# PANEL.net
KiCad netlist of a schematic drawn in Altium Designer
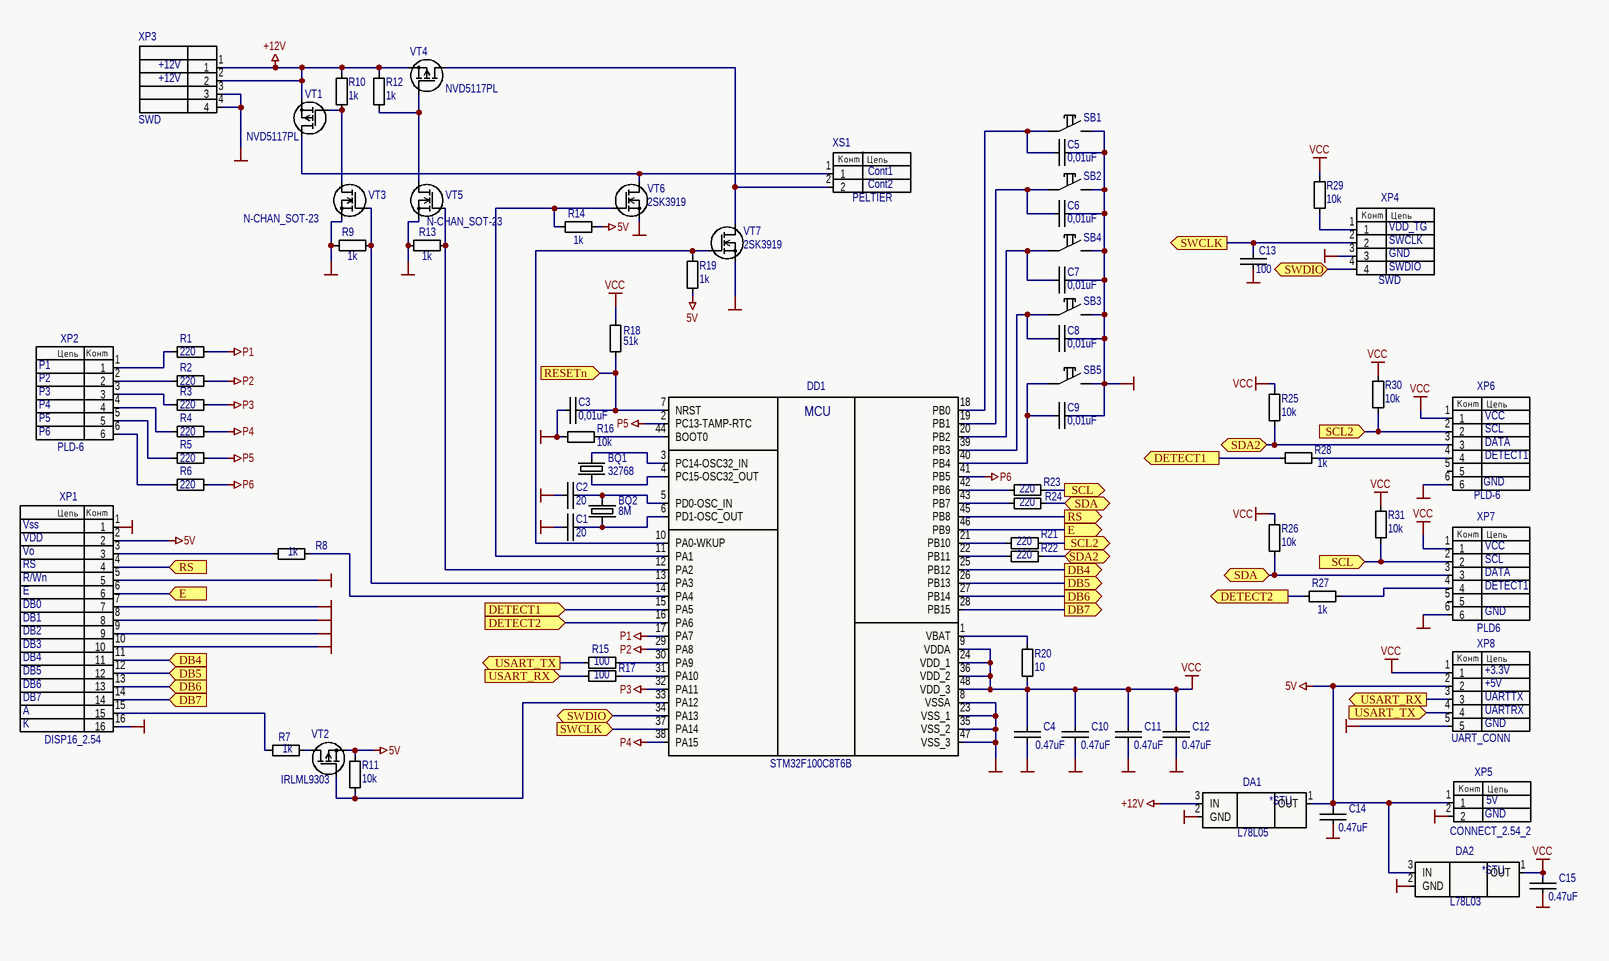
[diagram p0: PANEL.SchDoc]

(export (version "E")
  (design (tool "Eeschema 10.0.6"))
  (components
    (comp (ref "BQ1") (value "32768") (footprint "WatchQ") (libsource (lib "PANEL") (part "WatchQ")))
    (comp (ref "BQ2") (value "8M") (footprint "HC 49S") (libsource (lib "PANEL") (part "BQ_HC 49S")))
    (comp (ref "C1")
      (value "20")
      (footprint "Cap_0805")
      (fields (field (name "MANUFACTURER") "AVX") (field (name "PART NUMBER") "08051A200JAT2A"))
      (libsource (lib "PANEL") (part "Cap_0805"))
    )
    (comp (ref "C2")
      (value "20")
      (footprint "Cap_0805")
      (fields (field (name "MANUFACTURER") "AVX") (field (name "PART NUMBER") "08051A200JAT2A"))
      (libsource (lib "PANEL") (part "Cap_0805"))
    )
    (comp (ref "C3")
      (value "0,01uF")
      (footprint "Cap_0805")
      (fields (field (name "MANUFACTURER") "AVX") (field (name "PART NUMBER") "08055C103JAT2A"))
      (libsource (lib "PANEL") (part "Cap_0805"))
    )
    (comp (ref "C4")
      (value "0.47uF")
      (footprint "Cap_0805")
      (fields (field (name "MANUFACTURER") "AVX") (field (name "PART NUMBER") "0805YC475KAT2A"))
      (libsource (lib "PANEL") (part "Cap_0805"))
    )
    (comp (ref "C5")
      (value "0,01uF")
      (footprint "Cap_0805")
      (fields (field (name "MANUFACTURER") "AVX") (field (name "PART NUMBER") "08055C103JAT2A"))
      (libsource (lib "PANEL") (part "Cap_0805"))
    )
    (comp (ref "C6")
      (value "0,01uF")
      (footprint "Cap_0805")
      (fields (field (name "MANUFACTURER") "AVX") (field (name "PART NUMBER") "08055C103JAT2A"))
      (libsource (lib "PANEL") (part "Cap_0805"))
    )
    (comp (ref "C7")
      (value "0,01uF")
      (footprint "Cap_0805")
      (fields (field (name "MANUFACTURER") "AVX") (field (name "PART NUMBER") "08055C103JAT2A"))
      (libsource (lib "PANEL") (part "Cap_0805"))
    )
    (comp (ref "C8")
      (value "0,01uF")
      (footprint "Cap_0805")
      (fields (field (name "MANUFACTURER") "AVX") (field (name "PART NUMBER") "08055C103JAT2A"))
      (libsource (lib "PANEL") (part "Cap_0805"))
    )
    (comp (ref "C9")
      (value "0,01uF")
      (footprint "Cap_0805")
      (fields (field (name "MANUFACTURER") "AVX") (field (name "PART NUMBER") "08055C103JAT2A"))
      (libsource (lib "PANEL") (part "Cap_0805"))
    )
    (comp (ref "C10")
      (value "0.47uF")
      (footprint "Cap_0805")
      (fields (field (name "MANUFACTURER") "AVX") (field (name "PART NUMBER") "0805YC475KAT2A"))
      (libsource (lib "PANEL") (part "Cap_0805"))
    )
    (comp (ref "C11")
      (value "0.47uF")
      (footprint "Cap_0805")
      (fields (field (name "MANUFACTURER") "AVX") (field (name "PART NUMBER") "0805YC475KAT2A"))
      (libsource (lib "PANEL") (part "Cap_0805"))
    )
    (comp (ref "C12")
      (value "0.47uF")
      (footprint "Cap_0805")
      (fields (field (name "MANUFACTURER") "AVX") (field (name "PART NUMBER") "0805YC475KAT2A"))
      (libsource (lib "PANEL") (part "Cap_0805"))
    )
    (comp (ref "C13")
      (value "100")
      (footprint "Cap_0805")
      (fields (field (name "MANUFACTURER") "AVX") (field (name "PART NUMBER") "08055C101KAT2A"))
      (libsource (lib "PANEL") (part "Cap_0805"))
    )
    (comp (ref "C14")
      (value "0.47uF")
      (footprint "Cap_0805")
      (fields (field (name "MANUFACTURER") "AVX") (field (name "PART NUMBER") "0805YC475KAT2A"))
      (libsource (lib "PANEL") (part "Cap_0805"))
    )
    (comp (ref "C15")
      (value "0.47uF")
      (footprint "Cap_0805")
      (fields (field (name "MANUFACTURER") "AVX") (field (name "PART NUMBER") "0805YC475KAT2A"))
      (libsource (lib "PANEL") (part "Cap_0805"))
    )
    (comp (ref "DA1") (value "L78L05") (footprint "kren") (libsource (lib "PANEL") (part "kren")))
    (comp (ref "DA2")
      (value "L78L03")
      (footprint "kren")
      (fields (field (name "PART NUMBER") "L78L05"))
      (libsource (lib "PANEL") (part "kren"))
    )
    (comp (ref "DD1")
      (value "STM32F100C8T6B")
      (footprint "LQFP48")
      (fields (field (name "MANUFACTURER") "Manufacturer") (field (name "PART NUMBER") "Part Number"))
      (libsource (lib "PANEL") (part "STM32F100C8T6B"))
    )
    (comp (ref "R1") (value "220") (footprint "Res_0805") (libsource (lib "PANEL") (part "Res_0805")))
    (comp (ref "R2") (value "220") (footprint "Res_0805") (libsource (lib "PANEL") (part "Res_0805")))
    (comp (ref "R3") (value "220") (footprint "Res_0805") (libsource (lib "PANEL") (part "Res_0805")))
    (comp (ref "R4")
      (value "220")
      (footprint "Res_0805")
      (fields (field (name "MANUFACTURER") "Vishay") (field (name "PART NUMBER") "CRCW080510K0JNTA"))
      (libsource (lib "PANEL") (part "Res_0805"))
    )
    (comp (ref "R5")
      (value "220")
      (footprint "Res_0805")
      (fields (field (name "MANUFACTURER") "Vishay") (field (name "PART NUMBER") "CRCW080510K0JNTA"))
      (libsource (lib "PANEL") (part "Res_0805"))
    )
    (comp (ref "R6") (value "220") (footprint "Res_0805") (libsource (lib "PANEL") (part "Res_0805")))
    (comp (ref "R7") (value "1k") (footprint "Res_0805") (libsource (lib "PANEL") (part "Res_0805")))
    (comp (ref "R8") (value "1k") (footprint "Res_0805") (libsource (lib "PANEL") (part "Res_0805")))
    (comp (ref "R9") (value "1k") (footprint "Res_0805") (libsource (lib "PANEL") (part "Res_0805")))
    (comp (ref "R10")
      (value "1k")
      (footprint "Res_0805")
      (fields (field (name "MANUFACTURER") "Vishay") (field (name "PART NUMBER") "SMD 0805"))
      (libsource (lib "") (part "Res_0805_1"))
    )
    (comp (ref "R11")
      (value "10k")
      (footprint "Res_0805")
      (fields (field (name "MANUFACTURER") "Vishay") (field (name "PART NUMBER") "CRCW080510K0JNTA"))
      (libsource (lib "PANEL") (part "Res_0805"))
    )
    (comp (ref "R12") (value "1k") (footprint "Res_0805") (libsource (lib "") (part "Res_0805_1")))
    (comp (ref "R13") (value "1k") (footprint "Res_0805") (libsource (lib "PANEL") (part "Res_0805")))
    (comp (ref "R14")
      (value "1k")
      (footprint "Res_0805")
      (fields (field (name "PART NUMBER") "0805 1k"))
      (libsource (lib "PANEL") (part "Res_0805"))
    )
    (comp (ref "R15") (value "100") (footprint "Res_0805") (libsource (lib "PANEL") (part "Res_0805")))
    (comp (ref "R16")
      (value "10k")
      (footprint "Res_0805")
      (fields (field (name "MANUFACTURER") "Vishay") (field (name "PART NUMBER") "CRCW080510K0JNTA"))
      (libsource (lib "PANEL") (part "Res_0805"))
    )
    (comp (ref "R17") (value "100") (footprint "Res_0805") (libsource (lib "PANEL") (part "Res_0805")))
    (comp (ref "R18")
      (value "51k")
      (footprint "Res_0805")
      (fields (field (name "MANUFACTURER") "Vishay") (field (name "PART NUMBER") "CRCW08055K00JNTA"))
      (libsource (lib "PANEL") (part "Res_0805"))
    )
    (comp (ref "R19")
      (value "1k")
      (footprint "Res_0805")
      (fields (field (name "PART NUMBER") "0805 1k"))
      (libsource (lib "PANEL") (part "Res_0805"))
    )
    (comp (ref "R20")
      (value "10")
      (footprint "Res_0805")
      (fields (field (name "MANUFACTURER") "Vishay") (field (name "PART NUMBER") "CRCW080510R0FKEA"))
      (libsource (lib "PANEL") (part "Res_0805"))
    )
    (comp (ref "R21") (value "220") (footprint "Res_0805") (libsource (lib "PANEL") (part "Res_0805")))
    (comp (ref "R22") (value "220") (footprint "Res_0805") (libsource (lib "PANEL") (part "Res_0805")))
    (comp (ref "R23") (value "220") (footprint "Res_0805") (libsource (lib "PANEL") (part "Res_0805")))
    (comp (ref "R24") (value "220") (footprint "Res_0805") (libsource (lib "PANEL") (part "Res_0805")))
    (comp (ref "R25")
      (value "10k")
      (footprint "Res_0805")
      (fields (field (name "MANUFACTURER") "Vishay") (field (name "PART NUMBER") "CRCW080510K0JNTA"))
      (libsource (lib "PANEL") (part "Res_0805"))
    )
    (comp (ref "R26")
      (value "10k")
      (footprint "Res_0805")
      (fields (field (name "MANUFACTURER") "Vishay") (field (name "PART NUMBER") "CRCW080510K0JNTA"))
      (libsource (lib "PANEL") (part "Res_0805"))
    )
    (comp (ref "R27")
      (value "1k")
      (footprint "Res_0805")
      (fields (field (name "MANUFACTURER") "Vishay") (field (name "PART NUMBER") "CRCW080510K0JNTA"))
      (libsource (lib "PANEL") (part "Res_0805"))
    )
    (comp (ref "R28")
      (value "1k")
      (footprint "Res_0805")
      (fields (field (name "MANUFACTURER") "Vishay") (field (name "PART NUMBER") "CRCW080510K0JNTA"))
      (libsource (lib "PANEL") (part "Res_0805"))
    )
    (comp (ref "R29")
      (value "10k")
      (footprint "Res_0805")
      (fields (field (name "MANUFACTURER") "Vishay") (field (name "PART NUMBER") "CRCW080510K0JNTA"))
      (libsource (lib "PANEL") (part "Res_0805"))
    )
    (comp (ref "R30")
      (value "10k")
      (footprint "Res_0805")
      (fields (field (name "MANUFACTURER") "Vishay") (field (name "PART NUMBER") "CRCW080510K0JNTA"))
      (libsource (lib "PANEL") (part "Res_0805"))
    )
    (comp (ref "R31")
      (value "10k")
      (footprint "Res_0805")
      (fields (field (name "MANUFACTURER") "Vishay") (field (name "PART NUMBER") "CRCW080510K0JNTA"))
      (libsource (lib "PANEL") (part "Res_0805"))
    )
    (comp (ref "SB1")
      (value "TS A3PV 130")
      (footprint "TS A3PV 130")
      (description "Button")
      (libsource (lib "") (part "TS A3PV 130_1"))
    )
    (comp (ref "SB2")
      (value "TS A3PV 130")
      (footprint "TS A3PV 130")
      (description "Button")
      (libsource (lib "") (part "TS A3PV 130_2"))
    )
    (comp (ref "SB3")
      (value "TS A3PV 130")
      (footprint "TS A3PV 130")
      (description "Button")
      (libsource (lib "PANEL") (part "TS A3PV 130"))
    )
    (comp (ref "SB4")
      (value "TS A3PV 130")
      (footprint "TS A3PV 130")
      (description "Button")
      (libsource (lib "PANEL") (part "TS A3PV 130"))
    )
    (comp (ref "SB5")
      (value "TS A3PV 130")
      (footprint "TS A3PV 130")
      (description "Button")
      (libsource (lib "PANEL") (part "TS A3PV 130"))
    )
    (comp (ref "VT1") (value "NVD5117PL") (footprint "TO-252") (libsource (lib "") (part "P-CHAN_TO-252_1")))
    (comp (ref "VT2")
      (value "IRLML9303")
      (footprint "SOT-23")
      (fields (field (name "PART NUMBER") "IRLML9303TRPBF"))
      (libsource (lib "PSU") (part "P-CHAN_SOT-23"))
    )
    (comp (ref "VT3")
      (value "N-CHAN_SOT-23")
      (footprint "SOT-23")
      (libsource (lib "PANEL") (part "N-CHAN_SOT-23"))
    )
    (comp (ref "VT4")
      (value "NVD5117PL")
      (footprint "TO-252")
      (libsource (lib "PANEL") (part "P-CHAN_TO-252"))
    )
    (comp (ref "VT5")
      (value "N-CHAN_SOT-23")
      (footprint "SOT-23")
      (libsource (lib "PANEL") (part "N-CHAN_SOT-23"))
    )
    (comp (ref "VT6") (value "2SK3919") (footprint "TO-252") (libsource (lib "PANEL") (part "N-CHAN_TO-252")))
    (comp (ref "VT7") (value "2SK3919") (footprint "TO-252") (libsource (lib "PANEL") (part "N-CHAN_TO-252")))
    (comp (ref "XP1")
      (value "DISP16_2.54")
      (footprint "DISP16_2.54")
      (libsource (lib "PANEL") (part "DISP16_2.54"))
    )
    (comp (ref "XP2")
      (value "PLD-6")
      (footprint "CONN_2.54_6_2")
      (libsource (lib "PANEL") (part "CONNECT_2.54_6_2"))
    )
    (comp (ref "XP3")
      (value "SWD")
      (footprint "CONN_2.54_4")
      (fields (field (name "MANUFACTURER") "Manufacturer") (field (name "PART NUMBER") "Part Number"))
      (libsource (lib "PANEL") (part "CONNECT_SWD"))
    )
    (comp (ref "XP4")
      (value "SWD")
      (footprint "CONN_2.54_4")
      (fields (field (name "MANUFACTURER") "Manufacturer") (field (name "PART NUMBER") "Part Number"))
      (libsource (lib "") (part "CONNECT_SWD_1"))
    )
    (comp (ref "XP5")
      (value "CONNECT_2.54_2")
      (footprint "CONN_2.54_2")
      (libsource (lib "PANEL") (part "CONNECT_2.54_2"))
    )
    (comp (ref "XP6")
      (value "PLD-6")
      (footprint "CONN_2.54_6_2")
      (libsource (lib "PANEL") (part "CONNECT_2.54_6_2"))
    )
    (comp (ref "XP7")
      (value "PLD6")
      (footprint "CONN_2.54_6_2")
      (libsource (lib "PANEL") (part "CONNECT_2.54_6_2"))
    )
    (comp (ref "XP8")
      (value "UART_CONN")
      (footprint "CONN_2.54_5")
      (libsource (lib "PANEL") (part "CONNECT_2.54_5"))
    )
    (comp (ref "XS1") (value "PELTIER") (footprint "PELTIER") (libsource (lib "PANEL") (part "PELTIER")))
  )
  (nets
    (net (code "1") (name "+12V") (class "Default")
      (node (ref "DA1") (pin "3") (pinfunction "IN_3") (pintype "passive"))
      (node (ref "R10") (pin "1") (pinfunction "1_1") (pintype "passive"))
      (node (ref "R12") (pin "2") (pinfunction "2_2") (pintype "passive"))
      (node (ref "VT1") (pin "3") (pinfunction "3_3") (pintype "passive"))
      (node (ref "VT4") (pin "3") (pinfunction "3_3") (pintype "passive"))
      (node (ref "XP3") (pin "1") (pinfunction "1_1") (pintype "passive"))
      (node (ref "XP3") (pin "2") (pinfunction "2_2") (pintype "passive"))
    )
    (net (code "2") (name "/DB4") (class "Default")
      (node (ref "DD1") (pin "25") (pinfunction "PB12_25") (pintype "passive"))
      (node (ref "XP1") (pin "11") (pinfunction "11_11") (pintype "passive"))
    )
    (net (code "3") (name "/DB5") (class "Default")
      (node (ref "DD1") (pin "26") (pinfunction "PB13_26") (pintype "passive"))
      (node (ref "XP1") (pin "12") (pinfunction "12_12") (pintype "passive"))
    )
    (net (code "4") (name "/DB6") (class "Default")
      (node (ref "DD1") (pin "27") (pinfunction "PB14_27") (pintype "passive"))
      (node (ref "XP1") (pin "13") (pinfunction "13_13") (pintype "passive"))
    )
    (net (code "5") (name "/DB7") (class "Default")
      (node (ref "DD1") (pin "28") (pinfunction "PB15_28") (pintype "passive"))
      (node (ref "XP1") (pin "14") (pinfunction "14_14") (pintype "passive"))
    )
    (net (code "6") (name "/DETECT1") (class "Default")
      (node (ref "DD1") (pin "15") (pinfunction "PA5_15") (pintype "passive"))
      (node (ref "R28") (pin "2") (pinfunction "2_2") (pintype "passive"))
    )
    (net (code "7") (name "/DETECT2") (class "Default")
      (node (ref "DD1") (pin "16") (pinfunction "PA6_16") (pintype "passive"))
      (node (ref "R27") (pin "2") (pinfunction "2_2") (pintype "passive"))
    )
    (net (code "8") (name "/E") (class "Default")
      (node (ref "DD1") (pin "46") (pinfunction "PB9_46") (pintype "passive"))
      (node (ref "XP1") (pin "6") (pinfunction "6_6") (pintype "passive"))
    )
    (net (code "9") (name "/RESETn") (class "Default")
      (node (ref "C3") (pin "2") (pinfunction "2_2") (pintype "passive"))
      (node (ref "DD1") (pin "7") (pinfunction "NRST_7") (pintype "passive"))
      (node (ref "R18") (pin "1") (pinfunction "1_1") (pintype "passive"))
    )
    (net (code "10") (name "/RS") (class "Default")
      (node (ref "DD1") (pin "45") (pinfunction "PB8_45") (pintype "passive"))
      (node (ref "XP1") (pin "4") (pinfunction "4_4") (pintype "passive"))
    )
    (net (code "11") (name "/SCL") (class "Default")
      (node (ref "R23") (pin "1") (pinfunction "1_1") (pintype "passive"))
      (node (ref "R31") (pin "1") (pinfunction "1_1") (pintype "passive"))
      (node (ref "XP7") (pin "2") (pinfunction "2_2") (pintype "passive"))
    )
    (net (code "12") (name "/SCL2") (class "Default")
      (node (ref "R21") (pin "1") (pinfunction "1_1") (pintype "passive"))
      (node (ref "R30") (pin "1") (pinfunction "1_1") (pintype "passive"))
      (node (ref "XP6") (pin "2") (pinfunction "2_2") (pintype "passive"))
    )
    (net (code "13") (name "/SDA") (class "Default")
      (node (ref "R24") (pin "1") (pinfunction "1_1") (pintype "passive"))
      (node (ref "R26") (pin "1") (pinfunction "1_1") (pintype "passive"))
      (node (ref "XP7") (pin "3") (pinfunction "3_3") (pintype "passive"))
    )
    (net (code "14") (name "/SDA2") (class "Default")
      (node (ref "R22") (pin "1") (pinfunction "1_1") (pintype "passive"))
      (node (ref "R25") (pin "1") (pinfunction "1_1") (pintype "passive"))
      (node (ref "XP6") (pin "3") (pinfunction "3_3") (pintype "passive"))
    )
    (net (code "15") (name "/SWCLK") (class "Default")
      (node (ref "C13") (pin "2") (pinfunction "2_2") (pintype "passive"))
      (node (ref "DD1") (pin "37") (pinfunction "PA14_37") (pintype "passive"))
      (node (ref "XP4") (pin "2") (pinfunction "2_2") (pintype "passive"))
    )
    (net (code "16") (name "/SWDIO") (class "Default")
      (node (ref "DD1") (pin "34") (pinfunction "PA13_34") (pintype "passive"))
      (node (ref "XP4") (pin "4") (pinfunction "4_4") (pintype "passive"))
    )
    (net (code "17") (name "/USART_RX") (class "Default")
      (node (ref "R17") (pin "1") (pinfunction "1_1") (pintype "passive"))
      (node (ref "XP8") (pin "3") (pinfunction "3_3") (pintype "passive"))
    )
    (net (code "18") (name "/USART_TX") (class "Default")
      (node (ref "R15") (pin "1") (pinfunction "1_1") (pintype "passive"))
      (node (ref "XP8") (pin "4") (pinfunction "4_4") (pintype "passive"))
    )
    (net (code "19") (name "5V") (class "Default")
      (node (ref "C14") (pin "2") (pinfunction "2_2") (pintype "passive"))
      (node (ref "DA1") (pin "1") (pinfunction "OUT_1") (pintype "passive"))
      (node (ref "DA2") (pin "3") (pinfunction "IN_3") (pintype "passive"))
      (node (ref "R11") (pin "1") (pinfunction "1_1") (pintype "passive"))
      (node (ref "R14") (pin "2") (pinfunction "2_2") (pintype "passive"))
      (node (ref "R19") (pin "1") (pinfunction "1_1") (pintype "passive"))
      (node (ref "VT2") (pin "2") (pinfunction "2_2") (pintype "passive"))
      (node (ref "XP1") (pin "2") (pinfunction "2_2") (pintype "passive"))
      (node (ref "XP5") (pin "1") (pinfunction "1_1") (pintype "passive"))
      (node (ref "XP8") (pin "2") (pinfunction "2_2") (pintype "passive"))
    )
    (net (code "20") (name "GND") (class "Default")
      (node (ref "C1") (pin "1") (pinfunction "1_1") (pintype "passive"))
      (node (ref "C10") (pin "1") (pinfunction "1_1") (pintype "passive"))
      (node (ref "C11") (pin "1") (pinfunction "1_1") (pintype "passive"))
      (node (ref "C12") (pin "1") (pinfunction "1_1") (pintype "passive"))
      (node (ref "C13") (pin "1") (pinfunction "1_1") (pintype "passive"))
      (node (ref "C14") (pin "1") (pinfunction "1_1") (pintype "passive"))
      (node (ref "C15") (pin "1") (pinfunction "1_1") (pintype "passive"))
      (node (ref "C2") (pin "1") (pinfunction "1_1") (pintype "passive"))
      (node (ref "C3") (pin "1") (pinfunction "1_1") (pintype "passive"))
      (node (ref "C4") (pin "1") (pinfunction "1_1") (pintype "passive"))
      (node (ref "C5") (pin "2") (pinfunction "2_2") (pintype "passive"))
      (node (ref "C6") (pin "2") (pinfunction "2_2") (pintype "passive"))
      (node (ref "C7") (pin "2") (pinfunction "2_2") (pintype "passive"))
      (node (ref "C8") (pin "2") (pinfunction "2_2") (pintype "passive"))
      (node (ref "C9") (pin "2") (pinfunction "2_2") (pintype "passive"))
      (node (ref "DA1") (pin "2") (pinfunction "GND_2") (pintype "passive"))
      (node (ref "DA2") (pin "2") (pinfunction "GND_2") (pintype "passive"))
      (node (ref "DD1") (pin "23") (pinfunction "VSS_1_23") (pintype "passive"))
      (node (ref "DD1") (pin "35") (pinfunction "VSS_2_35") (pintype "passive"))
      (node (ref "DD1") (pin "47") (pinfunction "VSS_3_47") (pintype "passive"))
      (node (ref "DD1") (pin "8") (pinfunction "VSSA_8") (pintype "passive"))
      (node (ref "R13") (pin "1") (pinfunction "1_1") (pintype "passive"))
      (node (ref "R16") (pin "2") (pinfunction "2_2") (pintype "passive"))
      (node (ref "R9") (pin "2") (pinfunction "2_2") (pintype "passive"))
      (node (ref "SB1") (pin "2") (pinfunction "IN_2") (pintype "passive"))
      (node (ref "SB2") (pin "2") (pinfunction "IN_2") (pintype "passive"))
      (node (ref "SB3") (pin "2") (pinfunction "IN_2") (pintype "passive"))
      (node (ref "SB4") (pin "2") (pinfunction "IN_2") (pintype "passive"))
      (node (ref "SB5") (pin "2") (pinfunction "IN_2") (pintype "passive"))
      (node (ref "VT3") (pin "2") (pinfunction "2_2") (pintype "passive"))
      (node (ref "VT5") (pin "2") (pinfunction "2_2") (pintype "passive"))
      (node (ref "VT6") (pin "3") (pinfunction "3_3") (pintype "passive"))
      (node (ref "VT7") (pin "3") (pinfunction "3_3") (pintype "passive"))
      (node (ref "XP1") (pin "1") (pinfunction "1_1") (pintype "passive"))
      (node (ref "XP1") (pin "10") (pinfunction "10_10") (pintype "passive"))
      (node (ref "XP1") (pin "16") (pinfunction "16_16") (pintype "passive"))
      (node (ref "XP1") (pin "5") (pinfunction "5_5") (pintype "passive"))
      (node (ref "XP1") (pin "7") (pinfunction "7_7") (pintype "passive"))
      (node (ref "XP1") (pin "8") (pinfunction "8_8") (pintype "passive"))
      (node (ref "XP1") (pin "9") (pinfunction "9_9") (pintype "passive"))
      (node (ref "XP3") (pin "3") (pinfunction "3_3") (pintype "passive"))
      (node (ref "XP3") (pin "4") (pinfunction "4_4") (pintype "passive"))
      (node (ref "XP4") (pin "3") (pinfunction "3_3") (pintype "passive"))
      (node (ref "XP5") (pin "2") (pinfunction "2_2") (pintype "passive"))
      (node (ref "XP6") (pin "6") (pinfunction "6_6") (pintype "passive"))
      (node (ref "XP7") (pin "6") (pinfunction "6_6") (pintype "passive"))
      (node (ref "XP8") (pin "5") (pinfunction "5_5") (pintype "passive"))
    )
    (net (code "21") (name "Net-(DD1-BOOT0)") (class "Default")
      (node (ref "DD1") (pin "44") (pinfunction "BOOT0_44") (pintype "passive"))
      (node (ref "R16") (pin "1") (pinfunction "1_1") (pintype "passive"))
    )
    (net (code "22") (name "Net-(DD1-PA0-WKUP)") (class "Default")
      (node (ref "DD1") (pin "10") (pinfunction "PA0-WKUP_10") (pintype "passive"))
      (node (ref "R19") (pin "2") (pinfunction "2_2") (pintype "passive"))
      (node (ref "VT7") (pin "1") (pinfunction "1_1") (pintype "passive"))
    )
    (net (code "23") (name "Net-(DD1-PA1)") (class "Default")
      (node (ref "DD1") (pin "11") (pinfunction "PA1_11") (pintype "passive"))
      (node (ref "R14") (pin "1") (pinfunction "1_1") (pintype "passive"))
      (node (ref "VT6") (pin "1") (pinfunction "1_1") (pintype "passive"))
    )
    (net (code "24") (name "Net-(DD1-PA2)") (class "Default")
      (node (ref "DD1") (pin "12") (pinfunction "PA2_12") (pintype "passive"))
      (node (ref "R13") (pin "2") (pinfunction "2_2") (pintype "passive"))
      (node (ref "VT5") (pin "1") (pinfunction "1_1") (pintype "passive"))
    )
    (net (code "25") (name "Net-(DD1-PA3)") (class "Default")
      (node (ref "DD1") (pin "13") (pinfunction "PA3_13") (pintype "passive"))
      (node (ref "R9") (pin "1") (pinfunction "1_1") (pintype "passive"))
      (node (ref "VT3") (pin "1") (pinfunction "1_1") (pintype "passive"))
    )
    (net (code "26") (name "Net-(DD1-PA4)") (class "Default")
      (node (ref "DD1") (pin "14") (pinfunction "PA4_14") (pintype "passive"))
      (node (ref "R8") (pin "1") (pinfunction "1_1") (pintype "passive"))
    )
    (net (code "27") (name "Net-(DD1-PA9)") (class "Default")
      (node (ref "DD1") (pin "30") (pinfunction "PA9_30") (pintype "passive"))
      (node (ref "R15") (pin "2") (pinfunction "2_2") (pintype "passive"))
    )
    (net (code "28") (name "Net-(DD1-PA10)") (class "Default")
      (node (ref "DD1") (pin "31") (pinfunction "PA10_31") (pintype "passive"))
      (node (ref "R17") (pin "2") (pinfunction "2_2") (pintype "passive"))
    )
    (net (code "29") (name "Net-(DD1-PA12)") (class "Default")
      (node (ref "DD1") (pin "33") (pinfunction "PA12_33") (pintype "passive"))
      (node (ref "R11") (pin "2") (pinfunction "2_2") (pintype "passive"))
      (node (ref "VT2") (pin "1") (pinfunction "1_1") (pintype "passive"))
    )
    (net (code "30") (name "Net-(DD1-PB0)") (class "Default")
      (node (ref "C5") (pin "1") (pinfunction "1_1") (pintype "passive"))
      (node (ref "DD1") (pin "18") (pinfunction "PB0_18") (pintype "passive"))
      (node (ref "SB1") (pin "1") (pinfunction "OUT_1") (pintype "passive"))
    )
    (net (code "31") (name "Net-(DD1-PB1)") (class "Default")
      (node (ref "C6") (pin "1") (pinfunction "1_1") (pintype "passive"))
      (node (ref "DD1") (pin "19") (pinfunction "PB1_19") (pintype "passive"))
      (node (ref "SB2") (pin "1") (pinfunction "OUT_1") (pintype "passive"))
    )
    (net (code "32") (name "Net-(DD1-PB2)") (class "Default")
      (node (ref "C7") (pin "1") (pinfunction "1_1") (pintype "passive"))
      (node (ref "DD1") (pin "20") (pinfunction "PB2_20") (pintype "passive"))
      (node (ref "SB4") (pin "1") (pinfunction "OUT_1") (pintype "passive"))
    )
    (net (code "33") (name "Net-(DD1-PB3)") (class "Default")
      (node (ref "C8") (pin "1") (pinfunction "1_1") (pintype "passive"))
      (node (ref "DD1") (pin "39") (pinfunction "PB3_39") (pintype "passive"))
      (node (ref "SB3") (pin "1") (pinfunction "OUT_1") (pintype "passive"))
    )
    (net (code "34") (name "Net-(DD1-PB4)") (class "Default")
      (node (ref "C9") (pin "1") (pinfunction "1_1") (pintype "passive"))
      (node (ref "DD1") (pin "40") (pinfunction "PB4_40") (pintype "passive"))
      (node (ref "SB5") (pin "1") (pinfunction "OUT_1") (pintype "passive"))
    )
    (net (code "35") (name "Net-(DD1-PB6)") (class "Default")
      (node (ref "DD1") (pin "42") (pinfunction "PB6_42") (pintype "passive"))
      (node (ref "R23") (pin "2") (pinfunction "2_2") (pintype "passive"))
    )
    (net (code "36") (name "Net-(DD1-PB7)") (class "Default")
      (node (ref "DD1") (pin "43") (pinfunction "PB7_43") (pintype "passive"))
      (node (ref "R24") (pin "2") (pinfunction "2_2") (pintype "passive"))
    )
    (net (code "37") (name "Net-(DD1-PB10)") (class "Default")
      (node (ref "DD1") (pin "21") (pinfunction "PB10_21") (pintype "passive"))
      (node (ref "R21") (pin "2") (pinfunction "2_2") (pintype "passive"))
    )
    (net (code "38") (name "Net-(DD1-PB11)") (class "Default")
      (node (ref "DD1") (pin "22") (pinfunction "PB11_22") (pintype "passive"))
      (node (ref "R22") (pin "2") (pinfunction "2_2") (pintype "passive"))
    )
    (net (code "39") (name "Net-(DD1-PC14-OSC32_IN)") (class "Default")
      (node (ref "BQ1") (pin "1") (pinfunction "1_1") (pintype "passive"))
      (node (ref "DD1") (pin "3") (pinfunction "PC14-OSC32_IN_3") (pintype "passive"))
    )
    (net (code "40") (name "Net-(DD1-PC15-OSC32_OUT)") (class "Default")
      (node (ref "BQ1") (pin "2") (pinfunction "2_2") (pintype "passive"))
      (node (ref "DD1") (pin "4") (pinfunction "PC15-OSC32_OUT_4") (pintype "passive"))
    )
    (net (code "41") (name "Net-(DD1-PD0-OSC_IN)") (class "Default")
      (node (ref "BQ2") (pin "2") (pinfunction "2_2") (pintype "passive"))
      (node (ref "C2") (pin "2") (pinfunction "2_2") (pintype "passive"))
      (node (ref "DD1") (pin "5") (pinfunction "PD0-OSC_IN_5") (pintype "passive"))
    )
    (net (code "42") (name "Net-(DD1-PD1-OSC_OUT)") (class "Default")
      (node (ref "BQ2") (pin "1") (pinfunction "1_1") (pintype "passive"))
      (node (ref "C1") (pin "2") (pinfunction "2_2") (pintype "passive"))
      (node (ref "DD1") (pin "6") (pinfunction "PD1-OSC_OUT_6") (pintype "passive"))
    )
    (net (code "43") (name "Net-(DD1-VBAT)") (class "Default")
      (node (ref "DD1") (pin "1") (pinfunction "VBAT_1") (pintype "passive"))
      (node (ref "R20") (pin "1") (pinfunction "1_1") (pintype "passive"))
    )
    (net (code "44") (name "Net-(R1-Pad1)") (class "Default")
      (node (ref "R1") (pin "1") (pinfunction "1_1") (pintype "passive"))
      (node (ref "XP2") (pin "1") (pinfunction "1_1") (pintype "passive"))
    )
    (net (code "45") (name "Net-(R2-Pad1)") (class "Default")
      (node (ref "R2") (pin "1") (pinfunction "1_1") (pintype "passive"))
      (node (ref "XP2") (pin "2") (pinfunction "2_2") (pintype "passive"))
    )
    (net (code "46") (name "Net-(R3-Pad1)") (class "Default")
      (node (ref "R3") (pin "1") (pinfunction "1_1") (pintype "passive"))
      (node (ref "XP2") (pin "3") (pinfunction "3_3") (pintype "passive"))
    )
    (net (code "47") (name "Net-(R4-Pad2)") (class "Default")
      (node (ref "R4") (pin "2") (pinfunction "2_2") (pintype "passive"))
      (node (ref "XP2") (pin "4") (pinfunction "4_4") (pintype "passive"))
    )
    (net (code "48") (name "Net-(R5-Pad2)") (class "Default")
      (node (ref "R5") (pin "2") (pinfunction "2_2") (pintype "passive"))
      (node (ref "XP2") (pin "5") (pinfunction "5_5") (pintype "passive"))
    )
    (net (code "49") (name "Net-(R6-Pad1)") (class "Default")
      (node (ref "R6") (pin "1") (pinfunction "1_1") (pintype "passive"))
      (node (ref "XP2") (pin "6") (pinfunction "6_6") (pintype "passive"))
    )
    (net (code "50") (name "Net-(R7-Pad1)") (class "Default")
      (node (ref "R7") (pin "1") (pinfunction "1_1") (pintype "passive"))
      (node (ref "VT2") (pin "3") (pinfunction "3_3") (pintype "passive"))
    )
    (net (code "51") (name "Net-(R7-Pad2)") (class "Default")
      (node (ref "R7") (pin "2") (pinfunction "2_2") (pintype "passive"))
      (node (ref "XP1") (pin "15") (pinfunction "15_15") (pintype "passive"))
    )
    (net (code "52") (name "Net-(R8-Pad2)") (class "Default")
      (node (ref "R8") (pin "2") (pinfunction "2_2") (pintype "passive"))
      (node (ref "XP1") (pin "3") (pinfunction "3_3") (pintype "passive"))
    )
    (net (code "53") (name "Net-(R10-Pad2)") (class "Default")
      (node (ref "R10") (pin "2") (pinfunction "2_2") (pintype "passive"))
      (node (ref "VT1") (pin "1") (pinfunction "1_1") (pintype "passive"))
      (node (ref "VT3") (pin "3") (pinfunction "3_3") (pintype "passive"))
    )
    (net (code "54") (name "Net-(R12-Pad1)") (class "Default")
      (node (ref "R12") (pin "1") (pinfunction "1_1") (pintype "passive"))
      (node (ref "VT4") (pin "1") (pinfunction "1_1") (pintype "passive"))
      (node (ref "VT5") (pin "3") (pinfunction "3_3") (pintype "passive"))
    )
    (net (code "55") (name "Net-(R27-Pad1)") (class "Default")
      (node (ref "R27") (pin "1") (pinfunction "1_1") (pintype "passive"))
      (node (ref "XP7") (pin "4") (pinfunction "4_4") (pintype "passive"))
    )
    (net (code "56") (name "Net-(R28-Pad1)") (class "Default")
      (node (ref "R28") (pin "1") (pinfunction "1_1") (pintype "passive"))
      (node (ref "XP6") (pin "4") (pinfunction "4_4") (pintype "passive"))
    )
    (net (code "57") (name "Net-(R29-Pad1)") (class "Default")
      (node (ref "R29") (pin "1") (pinfunction "1_1") (pintype "passive"))
      (node (ref "XP4") (pin "1") (pinfunction "1_1") (pintype "passive"))
    )
    (net (code "58") (name "Net-(VT1-Pad2)") (class "Default")
      (node (ref "VT1") (pin "2") (pinfunction "2_2") (pintype "passive"))
      (node (ref "VT6") (pin "2") (pinfunction "2_2") (pintype "passive"))
      (node (ref "XS1") (pin "1") (pinfunction "1_1") (pintype "passive"))
    )
    (net (code "59") (name "Net-(VT4-Pad2)") (class "Default")
      (node (ref "VT4") (pin "2") (pinfunction "2_2") (pintype "passive"))
      (node (ref "VT7") (pin "2") (pinfunction "2_2") (pintype "passive"))
      (node (ref "XS1") (pin "2") (pinfunction "2_2") (pintype "passive"))
    )
    (net (code "60") (name "P1") (class "Default")
      (node (ref "DD1") (pin "17") (pinfunction "PA7_17") (pintype "passive"))
      (node (ref "R1") (pin "2") (pinfunction "2_2") (pintype "passive"))
    )
    (net (code "61") (name "P2") (class "Default")
      (node (ref "DD1") (pin "29") (pinfunction "PA8_29") (pintype "passive"))
      (node (ref "R2") (pin "2") (pinfunction "2_2") (pintype "passive"))
    )
    (net (code "62") (name "P3") (class "Default")
      (node (ref "DD1") (pin "32") (pinfunction "PA11_32") (pintype "passive"))
      (node (ref "R3") (pin "2") (pinfunction "2_2") (pintype "passive"))
    )
    (net (code "63") (name "P4") (class "Default")
      (node (ref "DD1") (pin "38") (pinfunction "PA15_38") (pintype "passive"))
      (node (ref "R4") (pin "1") (pinfunction "1_1") (pintype "passive"))
    )
    (net (code "64") (name "P5") (class "Default")
      (node (ref "DD1") (pin "2") (pinfunction "PC13-TAMP-RTC_2") (pintype "passive"))
      (node (ref "R5") (pin "1") (pinfunction "1_1") (pintype "passive"))
    )
    (net (code "65") (name "P6") (class "Default")
      (node (ref "DD1") (pin "41") (pinfunction "PB5_41") (pintype "passive"))
      (node (ref "R6") (pin "2") (pinfunction "2_2") (pintype "passive"))
    )
    (net (code "66") (name "VCC") (class "Default")
      (node (ref "C10") (pin "2") (pinfunction "2_2") (pintype "passive"))
      (node (ref "C11") (pin "2") (pinfunction "2_2") (pintype "passive"))
      (node (ref "C12") (pin "2") (pinfunction "2_2") (pintype "passive"))
      (node (ref "C15") (pin "2") (pinfunction "2_2") (pintype "passive"))
      (node (ref "C4") (pin "2") (pinfunction "2_2") (pintype "passive"))
      (node (ref "DA2") (pin "1") (pinfunction "OUT_1") (pintype "passive"))
      (node (ref "DD1") (pin "24") (pinfunction "VDD_1_24") (pintype "passive"))
      (node (ref "DD1") (pin "36") (pinfunction "VDD_2_36") (pintype "passive"))
      (node (ref "DD1") (pin "48") (pinfunction "VDD_3_48") (pintype "passive"))
      (node (ref "DD1") (pin "9") (pinfunction "VDDA_9") (pintype "passive"))
      (node (ref "R18") (pin "2") (pinfunction "2_2") (pintype "passive"))
      (node (ref "R20") (pin "2") (pinfunction "2_2") (pintype "passive"))
      (node (ref "R25") (pin "2") (pinfunction "2_2") (pintype "passive"))
      (node (ref "R26") (pin "2") (pinfunction "2_2") (pintype "passive"))
      (node (ref "R29") (pin "2") (pinfunction "2_2") (pintype "passive"))
      (node (ref "R30") (pin "2") (pinfunction "2_2") (pintype "passive"))
      (node (ref "R31") (pin "2") (pinfunction "2_2") (pintype "passive"))
      (node (ref "XP6") (pin "1") (pinfunction "1_1") (pintype "passive"))
      (node (ref "XP7") (pin "1") (pinfunction "1_1") (pintype "passive"))
      (node (ref "XP8") (pin "1") (pinfunction "1_1") (pintype "passive"))
    )
    (net (code "67") (name "unconnected-(XP6-Pad5)") (class "Default")
      (node (ref "XP6") (pin "5") (pinfunction "5_5") (pintype "passive"))
    )
    (net (code "68") (name "unconnected-(XP7-Pad5)") (class "Default")
      (node (ref "XP7") (pin "5") (pinfunction "5_5") (pintype "passive"))
    )
  )
)
